# power5V.net
KiCad netlist of a schematic drawn in EAGLE
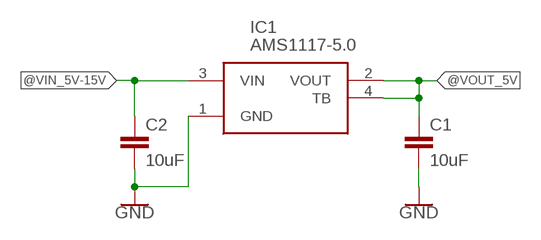
[diagram p0: schematic, sheet 1]

(export (version "E")
  (design (tool "Eeschema 10.0.6"))
  (components
    (comp (ref "C1")
      (value "10uF")
      (footprint "eagle-import:0603")
      (libsource (lib "eagle-import") (part "10UF-0603-6.3V-20%"))
    )
    (comp (ref "C2")
      (value "10uF")
      (footprint "eagle-import:0603")
      (libsource (lib "eagle-import") (part "10UF-0603-6.3V-20%"))
    )
    (comp (ref "IC1")
      (value "AMS1117-5.0")
      (footprint "eagle-import:SOT290P700X180-4N")
      (libsource (lib "eagle-import") (part "AMS1117-5.0"))
    )
  )
  (nets
    (net (code "1") (name "@VIN_5V-15V") (class "Default")
      (node (ref "C2") (pin "1") (pinfunction "1_1") (pintype "passive"))
      (node (ref "IC1") (pin "3") (pinfunction "VIN_3") (pintype "bidirectional"))
    )
    (net (code "2") (name "@VOUT_5V") (class "Default")
      (node (ref "C1") (pin "1") (pinfunction "1_1") (pintype "passive"))
      (node (ref "IC1") (pin "2") (pinfunction "VOUT_2") (pintype "bidirectional"))
      (node (ref "IC1") (pin "4") (pinfunction "TB_4") (pintype "bidirectional"))
    )
    (net (code "3") (name "GND") (class "Default")
      (node (ref "C1") (pin "2") (pinfunction "2_2") (pintype "passive"))
      (node (ref "C2") (pin "2") (pinfunction "2_2") (pintype "passive"))
      (node (ref "IC1") (pin "1") (pinfunction "GND_1") (pintype "bidirectional"))
    )
  )
)
